# Servo_Level_Shifter.net
KiCad netlist of a schematic drawn in Altium Designer
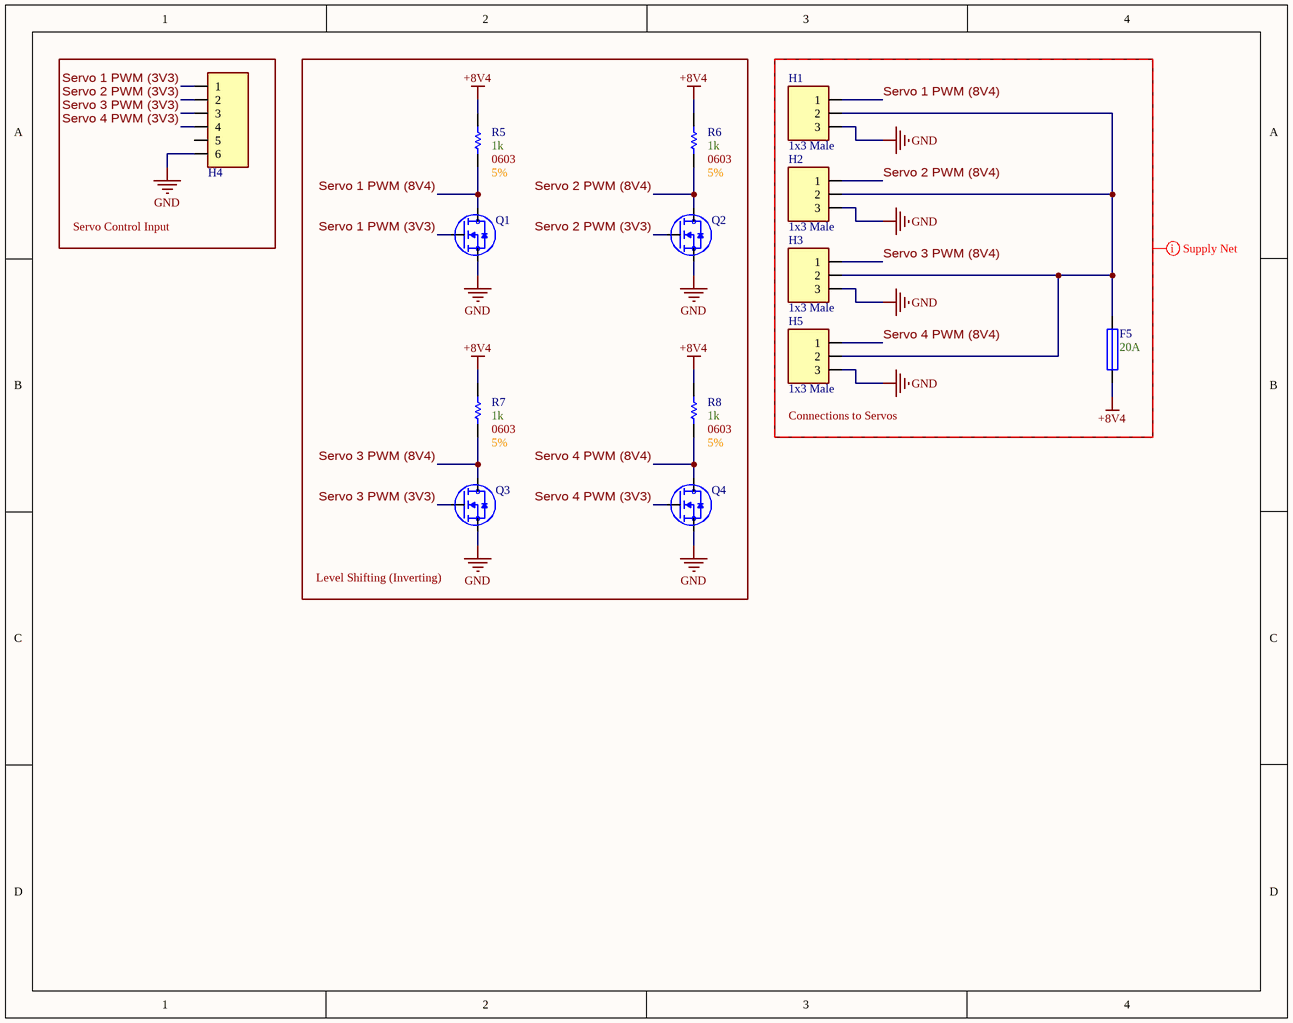
[diagram p0: Servo Level Shifter.SchDoc]

(export (version "E")
  (design (tool "Eeschema 10.0.6"))
  (components
    (comp (ref "F5")
      (value "Thru-Hole")
      (footprint "[Fuse] Thru-Hole Blade")
      (fields (field (name "CAPACITY") "20A"))
      (libsource (lib "RADM Components") (part "[Fuse] Thru-Hole Blade"))
    )
    (comp (ref "H1")
      (value "1x3 Male")
      (footprint "[Header] Shrouded 1x3 Male")
      (description "070543-0037\r\nMates with 005057-9403")
      (libsource (lib "RADM Connectors") (part "[Header] Shrouded 1x3 Male"))
    )
    (comp (ref "H2")
      (value "1x3 Male")
      (footprint "[Header] Shrouded 1x3 Male")
      (description "070543-0037\r\nMates with 005057-9403")
      (libsource (lib "RADM Connectors") (part "[Header] Shrouded 1x3 Male"))
    )
    (comp (ref "H3")
      (value "1x3 Male")
      (footprint "[Header] Shrouded 1x3 Male")
      (description "070543-0037\r\nMates with 005057-9403")
      (libsource (lib "RADM Connectors") (part "[Header] Shrouded 1x3 Male"))
    )
    (comp (ref "H4")
      (value "[Header] Shrouded 1x6 Male")
      (footprint "[Header] Shrouded 1x6 Male")
      (description "0705430005\r\nMates with 0050579406")
      (libsource (lib "RADM Connectors") (part "[Header] Shrouded 1x6 Male"))
    )
    (comp (ref "H5")
      (value "1x3 Male")
      (footprint "[Header] Shrouded 1x3 Male")
      (description "070543-0037\r\nMates with 005057-9403")
      (libsource (lib "RADM Connectors") (part "[Header] Shrouded 1x3 Male"))
    )
    (comp (ref "Q1")
      (value "DMG1012UW-7")
      (footprint "[FET] N-Channel Mosfet")
      (libsource (lib "RADM Components") (part "[FET] N-Channel MOSFET"))
    )
    (comp (ref "Q2")
      (value "DMG1012UW-7")
      (footprint "[FET] N-Channel Mosfet")
      (libsource (lib "RADM Components") (part "[FET] N-Channel MOSFET"))
    )
    (comp (ref "Q3")
      (value "DMG1012UW-7")
      (footprint "[FET] N-Channel Mosfet")
      (libsource (lib "RADM Components") (part "[FET] N-Channel MOSFET"))
    )
    (comp (ref "Q4")
      (value "DMG1012UW-7")
      (footprint "[FET] N-Channel Mosfet")
      (libsource (lib "RADM Components") (part "[FET] N-Channel MOSFET"))
    )
    (comp (ref "R5")
      (value "[Res] SMD Resistor")
      (footprint "[Res] SMD 0603")
      (description "Generic")
      (fields
        (field (name "TOLERANCE") "5%")
        (field (name "RESISTANCE") "1k")
        (field (name "SIZE PACKAGE") "0603")
      )
      (libsource (lib "RADM Components") (part "[Res] SMD Resistor"))
    )
    (comp (ref "R6")
      (value "[Res] SMD Resistor")
      (footprint "[Res] SMD 0603")
      (description "Generic")
      (fields
        (field (name "TOLERANCE") "5%")
        (field (name "RESISTANCE") "1k")
        (field (name "SIZE PACKAGE") "0603")
      )
      (libsource (lib "RADM Components") (part "[Res] SMD Resistor"))
    )
    (comp (ref "R7")
      (value "[Res] SMD Resistor")
      (footprint "[Res] SMD 0603")
      (description "Generic")
      (fields
        (field (name "TOLERANCE") "5%")
        (field (name "RESISTANCE") "1k")
        (field (name "SIZE PACKAGE") "0603")
      )
      (libsource (lib "RADM Components") (part "[Res] SMD Resistor"))
    )
    (comp (ref "R8")
      (value "[Res] SMD Resistor")
      (footprint "[Res] SMD 0603")
      (description "Generic")
      (fields
        (field (name "TOLERANCE") "5%")
        (field (name "RESISTANCE") "1k")
        (field (name "SIZE PACKAGE") "0603")
      )
      (libsource (lib "RADM Components") (part "[Res] SMD Resistor"))
    )
  )
  (nets
    (net (code "1") (name "+8V4") (class "Default")
      (node (ref "F5") (pin "1") (pinfunction "1_1") (pintype "passive"))
      (node (ref "R5") (pin "2") (pinfunction "2_2") (pintype "passive"))
      (node (ref "R6") (pin "2") (pinfunction "2_2") (pintype "passive"))
      (node (ref "R7") (pin "2") (pinfunction "2_2") (pintype "passive"))
      (node (ref "R8") (pin "2") (pinfunction "2_2") (pintype "passive"))
    )
    (net (code "2") (name "/Servo 1 PWM (3V3)") (class "Default")
      (node (ref "H4") (pin "1") (pinfunction "1_1") (pintype "passive"))
      (node (ref "Q1") (pin "1") (pinfunction "Gate_1") (pintype "passive"))
    )
    (net (code "3") (name "/Servo 1 PWM (8V4)") (class "Default")
      (node (ref "H1") (pin "1") (pinfunction "1_1") (pintype "passive"))
      (node (ref "Q1") (pin "3") (pinfunction "Drain_3") (pintype "passive"))
      (node (ref "R5") (pin "1") (pinfunction "1_1") (pintype "passive"))
    )
    (net (code "4") (name "/Servo 2 PWM (3V3)") (class "Default")
      (node (ref "H4") (pin "2") (pinfunction "2_2") (pintype "passive"))
      (node (ref "Q2") (pin "1") (pinfunction "Gate_1") (pintype "passive"))
    )
    (net (code "5") (name "/Servo 2 PWM (8V4)") (class "Default")
      (node (ref "H2") (pin "1") (pinfunction "1_1") (pintype "passive"))
      (node (ref "Q2") (pin "3") (pinfunction "Drain_3") (pintype "passive"))
      (node (ref "R6") (pin "1") (pinfunction "1_1") (pintype "passive"))
    )
    (net (code "6") (name "/Servo 3 PWM (3V3)") (class "Default")
      (node (ref "H4") (pin "3") (pinfunction "3_3") (pintype "passive"))
      (node (ref "Q3") (pin "1") (pinfunction "Gate_1") (pintype "passive"))
    )
    (net (code "7") (name "/Servo 3 PWM (8V4)") (class "Default")
      (node (ref "H3") (pin "1") (pinfunction "1_1") (pintype "passive"))
      (node (ref "Q3") (pin "3") (pinfunction "Drain_3") (pintype "passive"))
      (node (ref "R7") (pin "1") (pinfunction "1_1") (pintype "passive"))
    )
    (net (code "8") (name "/Servo 4 PWM (3V3)") (class "Default")
      (node (ref "H4") (pin "4") (pinfunction "4_4") (pintype "passive"))
      (node (ref "Q4") (pin "1") (pinfunction "Gate_1") (pintype "passive"))
    )
    (net (code "9") (name "/Servo 4 PWM (8V4)") (class "Default")
      (node (ref "H5") (pin "1") (pinfunction "1_1") (pintype "passive"))
      (node (ref "Q4") (pin "3") (pinfunction "Drain_3") (pintype "passive"))
      (node (ref "R8") (pin "1") (pinfunction "1_1") (pintype "passive"))
    )
    (net (code "10") (name "GND") (class "Default")
      (node (ref "H1") (pin "3") (pinfunction "3_3") (pintype "passive"))
      (node (ref "H2") (pin "3") (pinfunction "3_3") (pintype "passive"))
      (node (ref "H3") (pin "3") (pinfunction "3_3") (pintype "passive"))
      (node (ref "H4") (pin "6") (pinfunction "6_6") (pintype "passive"))
      (node (ref "H5") (pin "3") (pinfunction "3_3") (pintype "passive"))
      (node (ref "Q1") (pin "2") (pinfunction "Source_2") (pintype "passive"))
      (node (ref "Q2") (pin "2") (pinfunction "Source_2") (pintype "passive"))
      (node (ref "Q3") (pin "2") (pinfunction "Source_2") (pintype "passive"))
      (node (ref "Q4") (pin "2") (pinfunction "Source_2") (pintype "passive"))
    )
    (net (code "11") (name "Net-(F5-Pad2)") (class "Default")
      (node (ref "F5") (pin "2") (pinfunction "2_2") (pintype "passive"))
      (node (ref "H1") (pin "2") (pinfunction "2_2") (pintype "passive"))
      (node (ref "H2") (pin "2") (pinfunction "2_2") (pintype "passive"))
      (node (ref "H3") (pin "2") (pinfunction "2_2") (pintype "passive"))
      (node (ref "H5") (pin "2") (pinfunction "2_2") (pintype "passive"))
    )
    (net (code "12") (name "unconnected-(H4-Pad5)") (class "Default")
      (node (ref "H4") (pin "5") (pinfunction "5_5") (pintype "passive"))
    )
  )
)
